# ldos.net
KiCad netlist of a schematic drawn in EasyEDA Pro
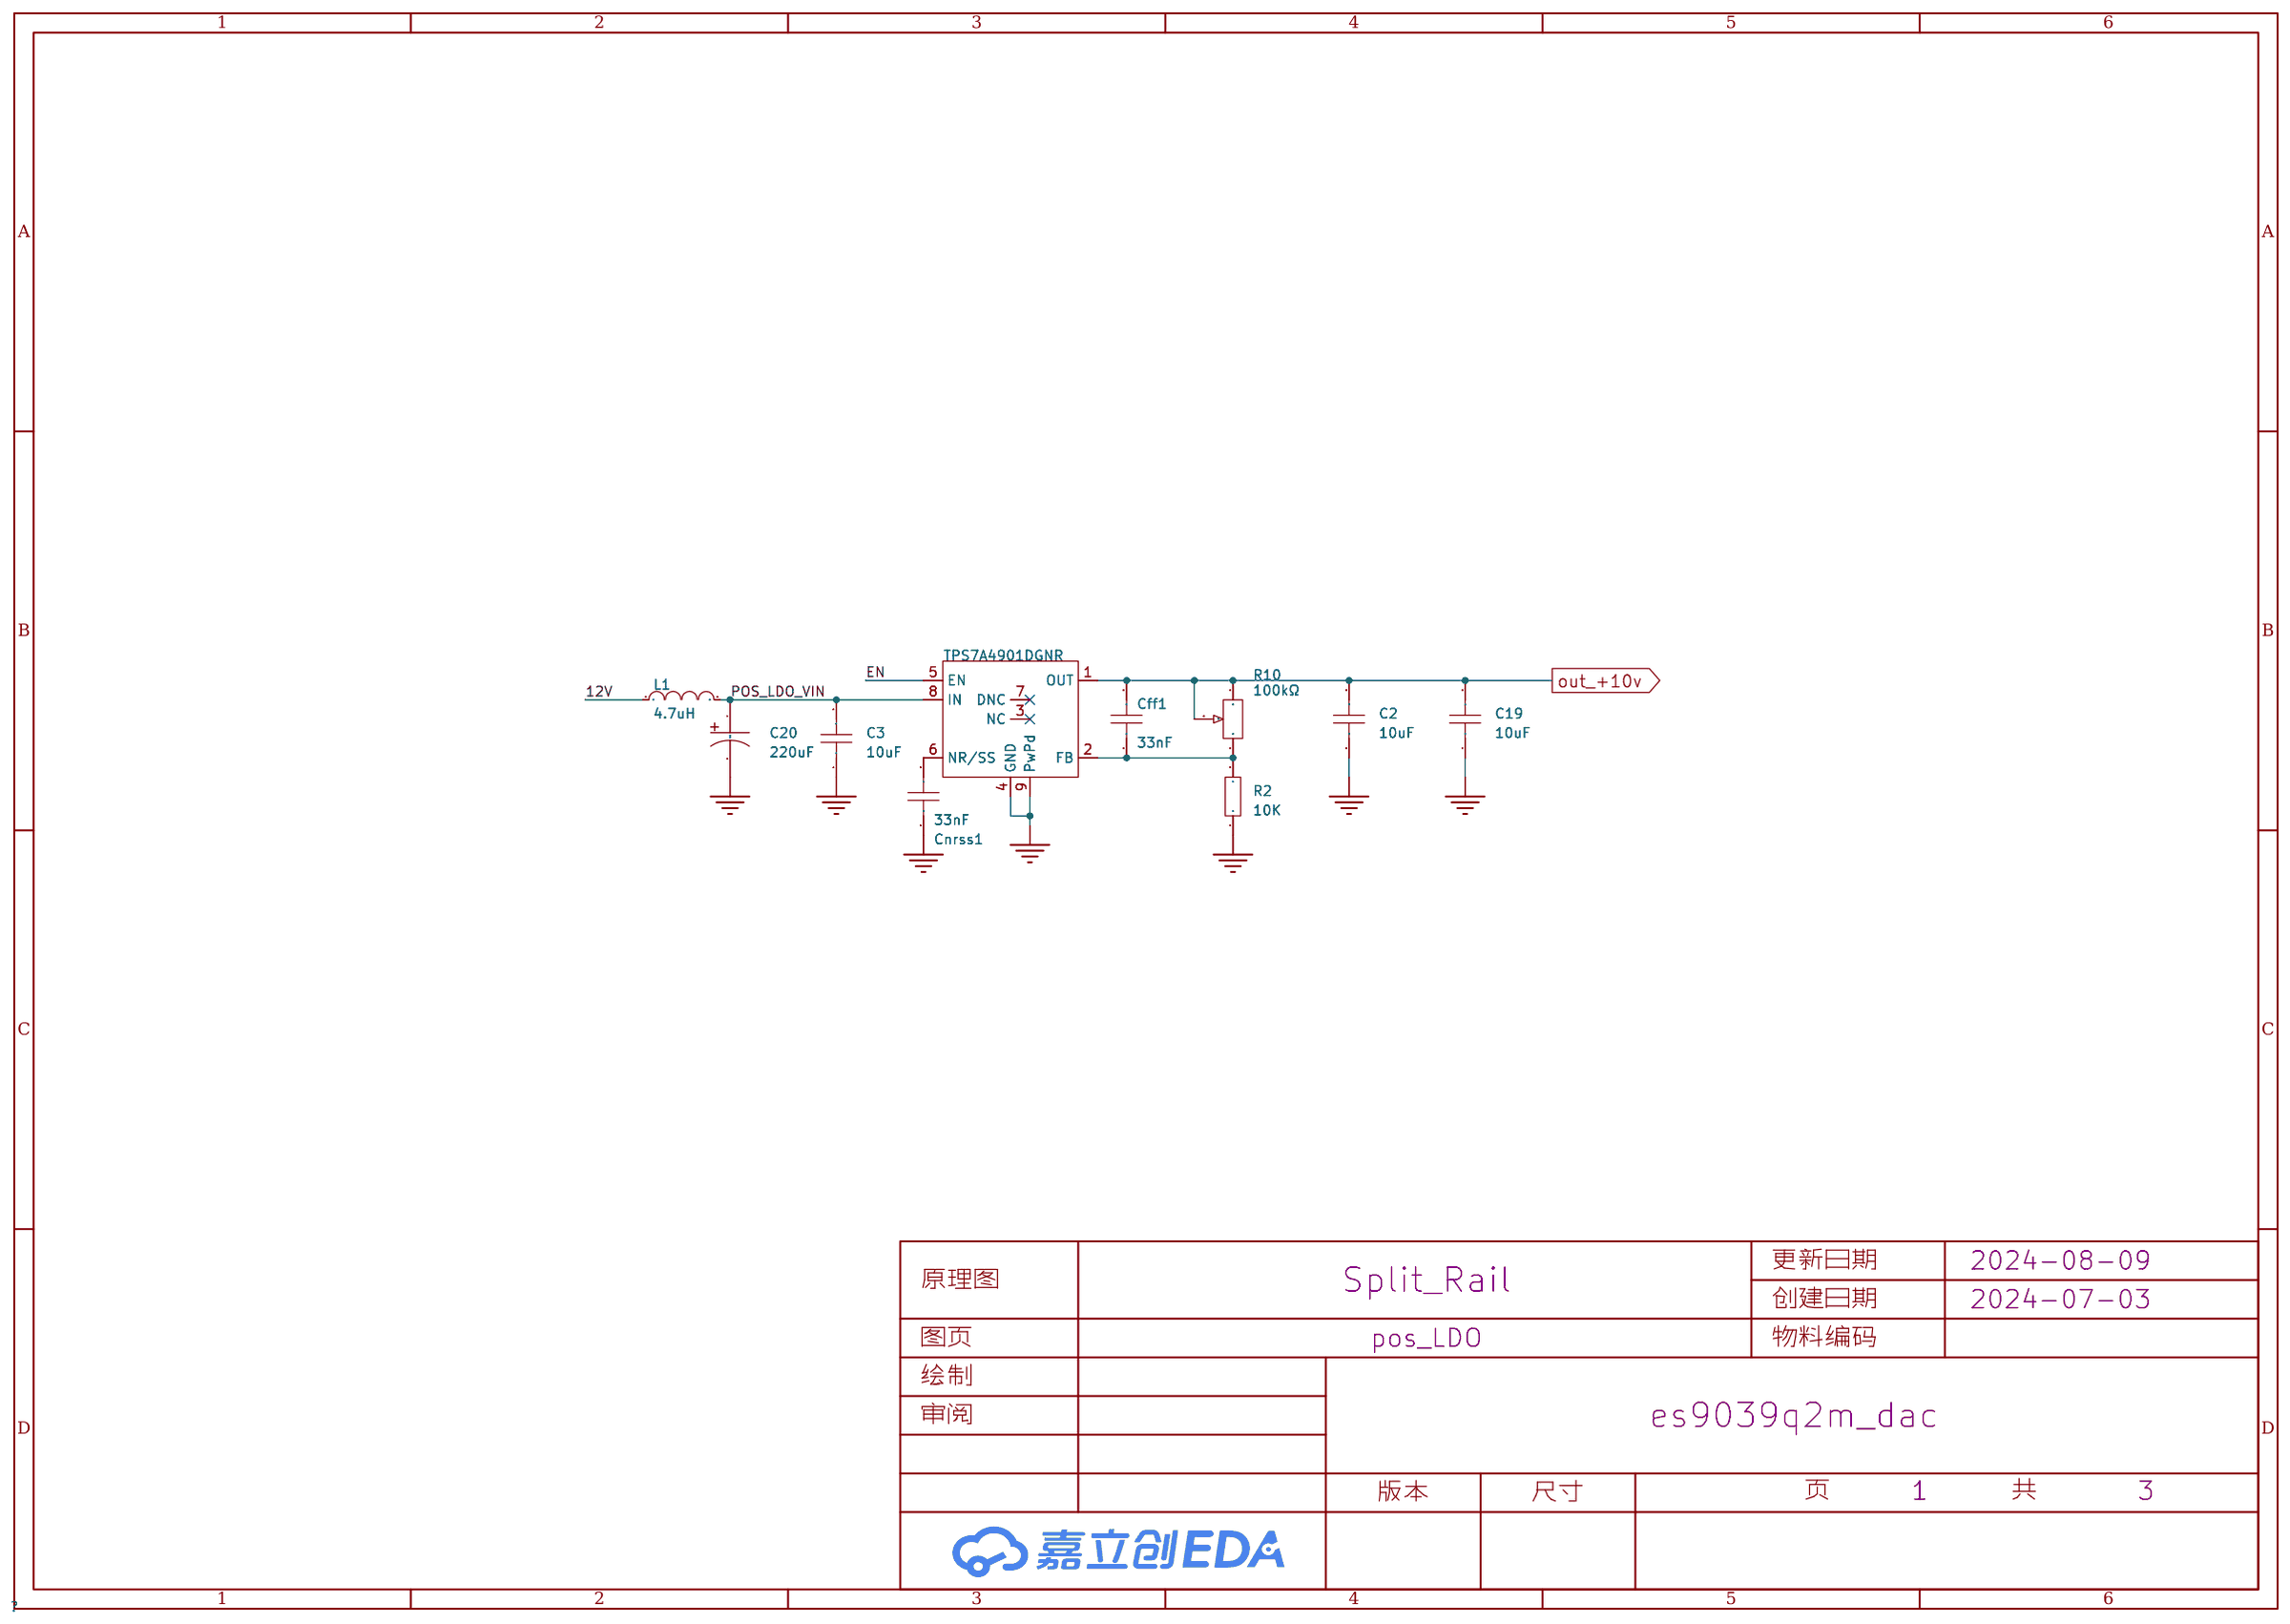
[diagram p0: pos_LDO]
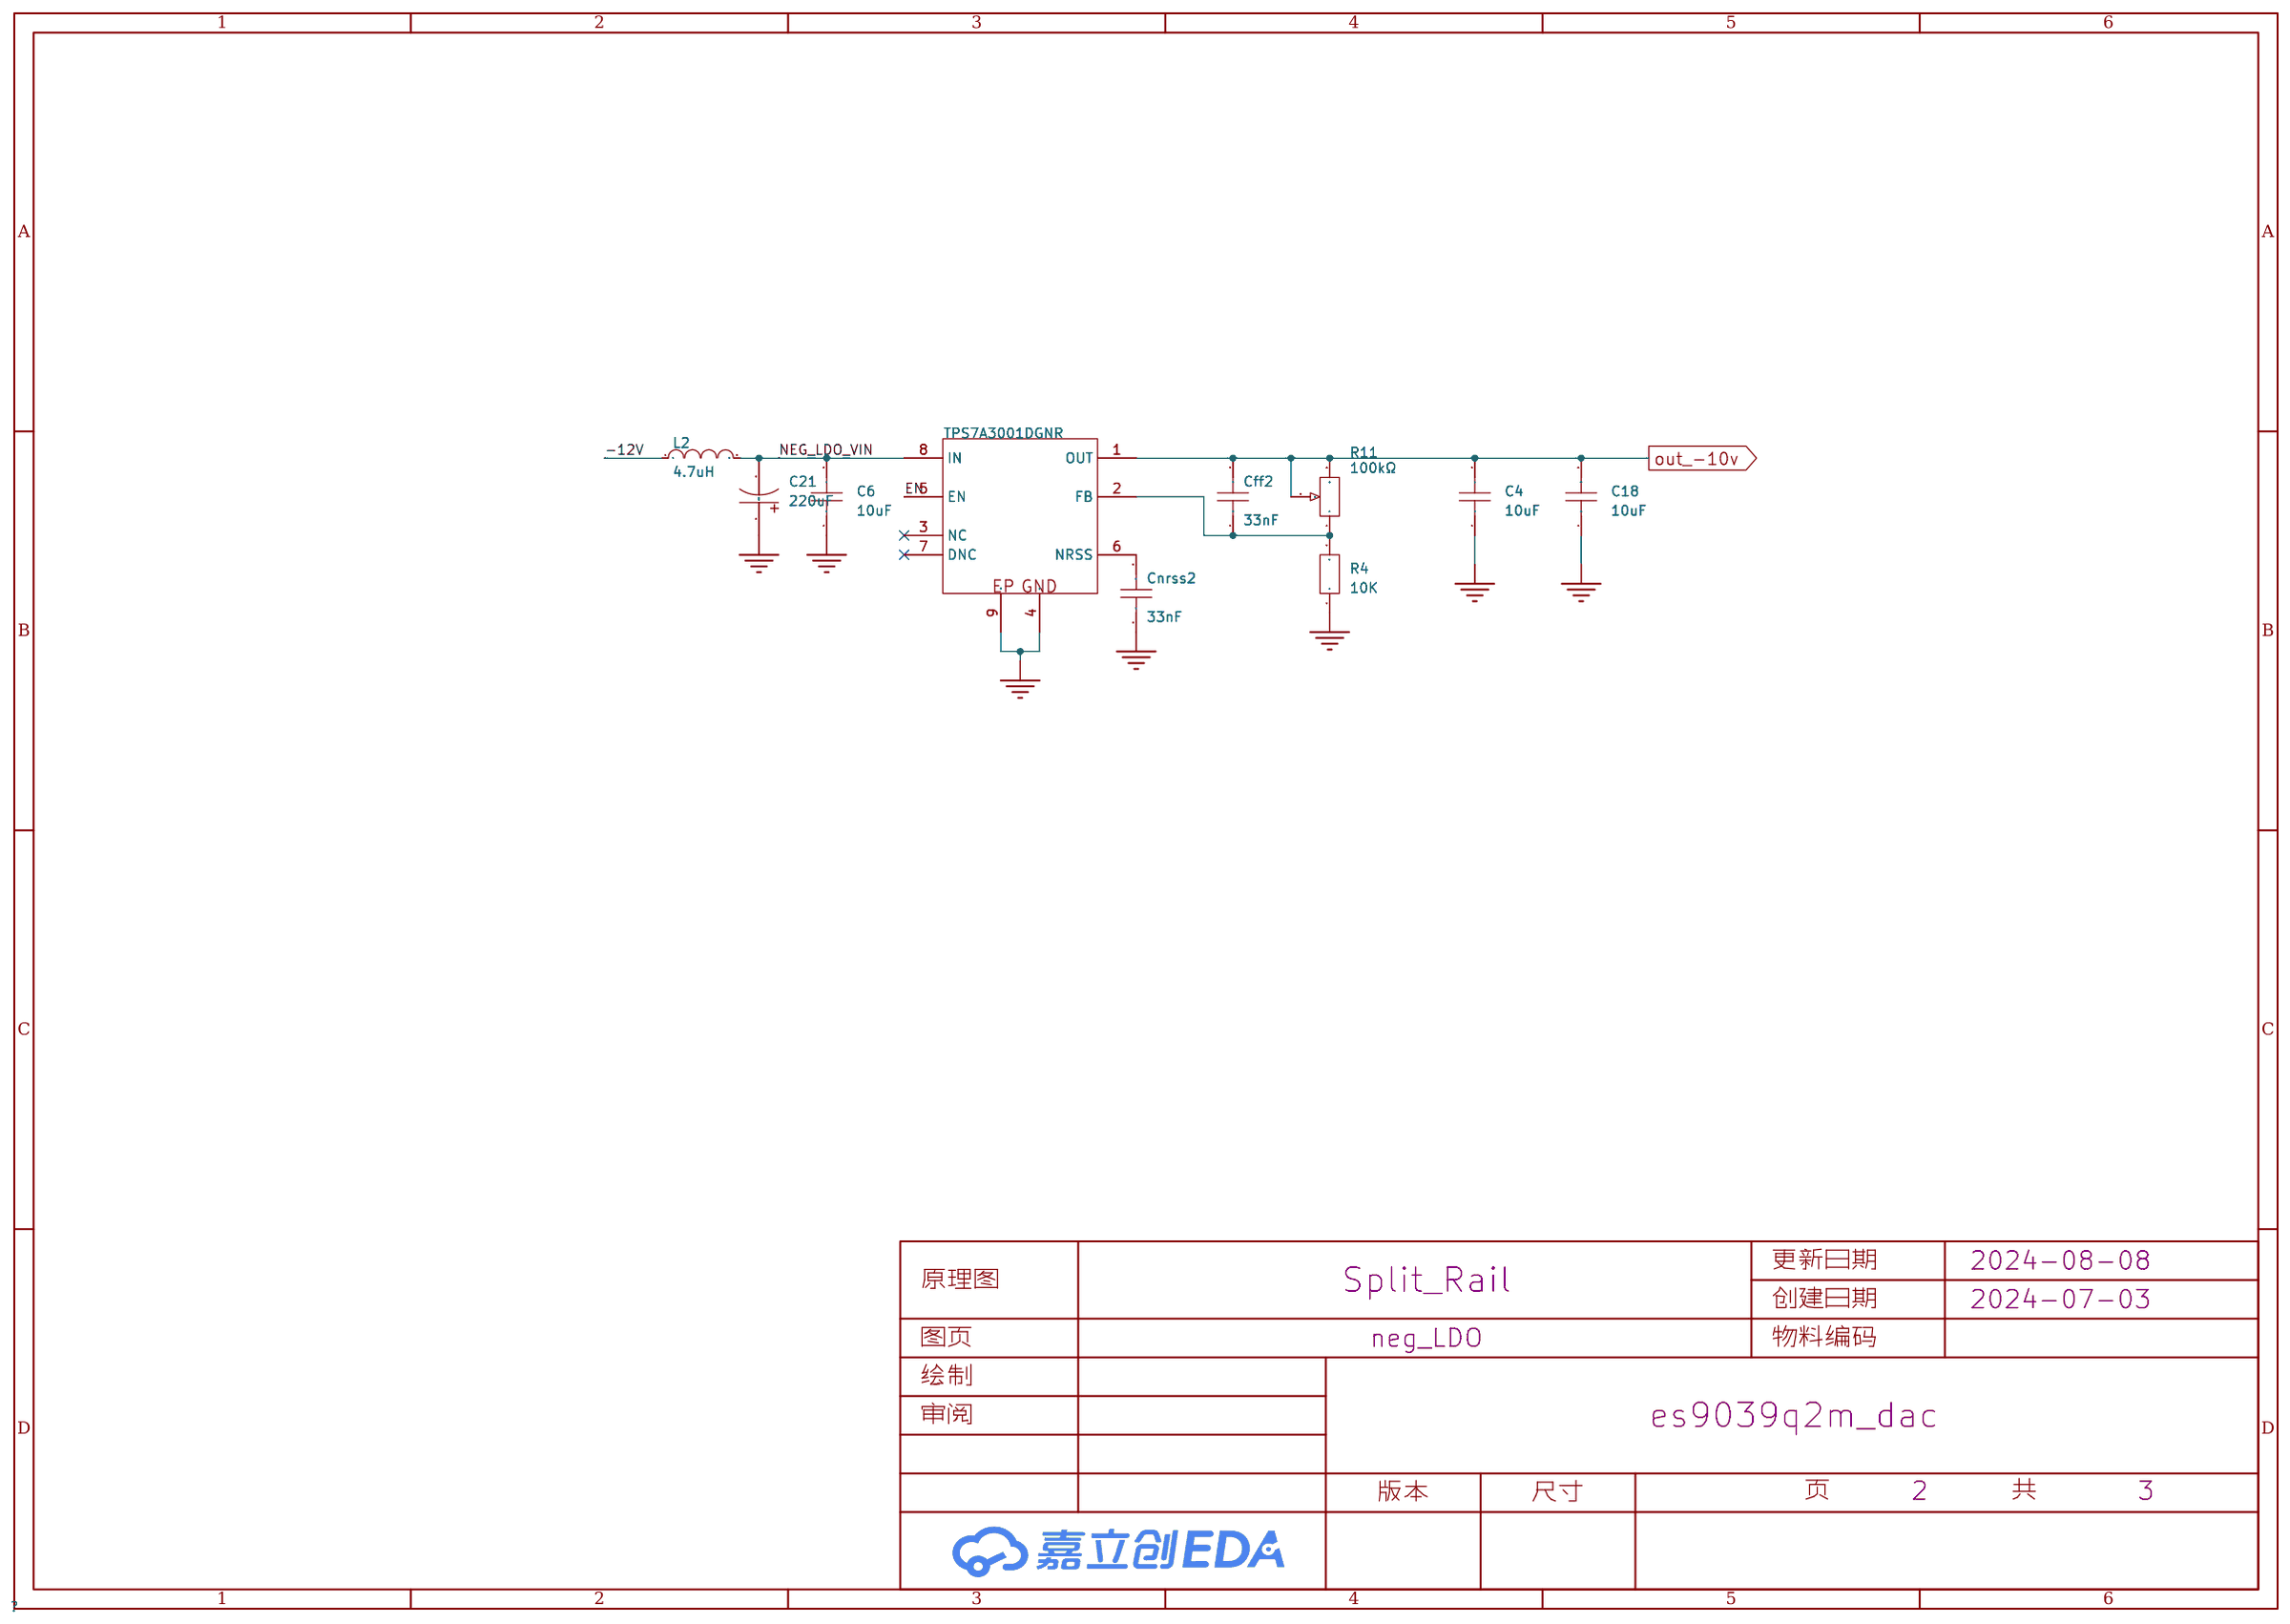
[diagram p1: neg_LDO]

(export (version "E")
  (design (tool "Eeschema 10.0.6"))
  (components
    (comp (ref "C2")
      (value "10uF")
      (footprint "easyedapro:C0805")
      (description "容值:10uF;精度:±10%;额定电压:16V;材质(温度系数):X7R;")
      (fields (field (name "Manufacturer Part") "0805B106K160NT") (field (name "Manufacturer") "FH(风华)"))
      (libsource (lib "easyedapro") (part "0805B106K160NT"))
    )
    (comp (ref "C3")
      (value "10uF")
      (footprint "easyedapro:C0805")
      (description "容值:10uF;精度:±10%;额定电压:16V;材质(温度系数):X7R;")
      (fields (field (name "Manufacturer Part") "0805B106K160NT") (field (name "Manufacturer") "FH(风华)"))
      (libsource (lib "easyedapro") (part "0805B106K160NT"))
    )
    (comp (ref "C19")
      (value "10uF")
      (footprint "easyedapro:C0805")
      (description "容值:10uF;精度:±10%;额定电压:16V;材质(温度系数):X7R;")
      (fields (field (name "Manufacturer Part") "0805B106K160NT") (field (name "Manufacturer") "FH(风华)"))
      (libsource (lib "easyedapro") (part "0805B106K160NT"))
    )
    (comp (ref "C20")
      (value "220uF")
      (footprint "easyedapro:CAP-TH_BD6.3-P2.50-D1.0-FD")
      (description "容值:220uF;精度:±20%;额定电压:16V;纹波电流:220mA@120Hz;等效串联电阻:-;")
      (fields
        (field (name "Manufacturer Part") "16PX220MEFC6.3*11")
        (field (name "Manufacturer") "rubycon(红宝石)")
      )
      (libsource (lib "easyedapro") (part "16PX220MEFC6.3*11"))
    )
    (comp (ref "Cff1")
      (value "33nF")
      (footprint "easyedapro:C1206")
      (description "容值:33nF;精度:±10%;额定电压:250V;材质(温度系数):X7R;")
      (fields
        (field (name "Manufacturer Part") "HHV1206R7333K251NSLJ")
        (field (name "Manufacturer") "Chinocera(华瓷)")
      )
      (libsource (lib "easyedapro") (part "HHV1206R7333K251NSLJ"))
    )
    (comp (ref "Cnrss1")
      (value "33nF")
      (footprint "easyedapro:C1206")
      (description "容值:33nF;精度:±10%;额定电压:250V;材质(温度系数):X7R;")
      (fields
        (field (name "Manufacturer Part") "HHV1206R7333K251NSLJ")
        (field (name "Manufacturer") "Chinocera(华瓷)")
      )
      (libsource (lib "easyedapro") (part "HHV1206R7333K251NSLJ"))
    )
    (comp (ref "L1")
      (value "4.7uH")
      (footprint "easyedapro:L1206")
      (description "电感值:4.7uH;精度:±10%;额定电流:25mA;饱和电流(Isat):-;直流电阻(DCR):650mΩ;")
      (fields (field (name "Manufacturer Part") "CMI321609U4R7KT") (field (name "Manufacturer") "FH(风华)"))
      (libsource (lib "easyedapro") (part "CMI321609U4R7KT"))
    )
    (comp (ref "R2") (value "10K") (footprint "easyedapro:R0603") (libsource (lib "easyedapro") (part "电阻")))
    (comp (ref "R10")
      (value "100kΩ")
      (footprint "easyedapro:RES-ADJ-TH_3P-L9.5-W4.9-P2.50-L_3296W")
      (description "阻值:100kΩ;精度:±10%;")
      (fields (field (name "Manufacturer Part") "3296W-1-104") (field (name "Manufacturer") "BOCHEN(博晨)"))
      (libsource (lib "easyedapro") (part "3296W-1-104"))
    )
    (comp (ref "U1")
      (value "TPS7A4901DGNR")
      (footprint "easyedapro:MSOP-8_L3.0-W3.0-P0.65-LS5.0-BL-EP")
      (description "输出类型:可调;最大输入电压:35V;输出电压:1.194V~33V;最大输出电流:150mA;电源纹波抑制比(PSRR):78dB@(1kHz);输出极性:正极;")
      (fields (field (name "Manufacturer") "TI(德州仪器)"))
      (libsource (lib "easyedapro") (part "TPS7A4901DGNR"))
    )
    (comp (ref "C4")
      (value "10uF")
      (footprint "easyedapro:C0805")
      (description "容值:10uF;精度:±10%;额定电压:16V;材质(温度系数):X7R;")
      (fields (field (name "Manufacturer Part") "0805B106K160NT") (field (name "Manufacturer") "FH(风华)"))
      (libsource (lib "easyedapro") (part "0805B106K160NT"))
    )
    (comp (ref "C6")
      (value "10uF")
      (footprint "easyedapro:C0805")
      (description "容值:10uF;精度:±10%;额定电压:16V;材质(温度系数):X7R;")
      (fields (field (name "Manufacturer Part") "0805B106K160NT") (field (name "Manufacturer") "FH(风华)"))
      (libsource (lib "easyedapro") (part "0805B106K160NT"))
    )
    (comp (ref "C18")
      (value "10uF")
      (footprint "easyedapro:C0805")
      (description "容值:10uF;精度:±10%;额定电压:16V;材质(温度系数):X7R;")
      (fields (field (name "Manufacturer Part") "0805B106K160NT") (field (name "Manufacturer") "FH(风华)"))
      (libsource (lib "easyedapro") (part "0805B106K160NT"))
    )
    (comp (ref "C21")
      (value "220uF")
      (footprint "easyedapro:CAP-TH_BD6.3-P2.50-D1.0-FD")
      (description "容值:220uF;精度:±20%;额定电压:16V;纹波电流:220mA@120Hz;等效串联电阻:-;")
      (fields
        (field (name "Manufacturer Part") "16PX220MEFC6.3*11")
        (field (name "Manufacturer") "rubycon(红宝石)")
      )
      (libsource (lib "easyedapro") (part "16PX220MEFC6.3*11"))
    )
    (comp (ref "Cff2")
      (value "33nF")
      (footprint "easyedapro:C1206")
      (description "容值:33nF;精度:±10%;额定电压:250V;材质(温度系数):X7R;")
      (fields
        (field (name "Manufacturer Part") "HHV1206R7333K251NSLJ")
        (field (name "Manufacturer") "Chinocera(华瓷)")
      )
      (libsource (lib "easyedapro") (part "HHV1206R7333K251NSLJ"))
    )
    (comp (ref "Cnrss2")
      (value "33nF")
      (footprint "easyedapro:C1206")
      (description "容值:33nF;精度:±10%;额定电压:250V;材质(温度系数):X7R;")
      (fields
        (field (name "Manufacturer Part") "HHV1206R7333K251NSLJ")
        (field (name "Manufacturer") "Chinocera(华瓷)")
      )
      (libsource (lib "easyedapro") (part "HHV1206R7333K251NSLJ"))
    )
    (comp (ref "L2")
      (value "4.7uH")
      (footprint "easyedapro:L1206")
      (description "电感值:4.7uH;精度:±10%;额定电流:25mA;饱和电流(Isat):-;直流电阻(DCR):650mΩ;")
      (fields (field (name "Manufacturer Part") "CMI321609U4R7KT") (field (name "Manufacturer") "FH(风华)"))
      (libsource (lib "easyedapro") (part "CMI321609U4R7KT"))
    )
    (comp (ref "R4") (value "10K") (libsource (lib "easyedapro") (part "RT0603BRD074K7L")))
    (comp (ref "R11")
      (value "100kΩ")
      (footprint "easyedapro:RES-ADJ-TH_3P-L9.5-W4.9-P2.50-L_3296W")
      (description "阻值:100kΩ;精度:±10%;")
      (fields (field (name "Manufacturer Part") "3296W-1-104") (field (name "Manufacturer") "BOCHEN(博晨)"))
      (libsource (lib "easyedapro") (part "3296W-1-104"))
    )
    (comp (ref "U2")
      (value "TPS7A3001DGNR")
      (footprint "easyedapro:MSOP-8_L3.0-W3.0-P0.65-LS5.0-BL-EP")
      (description "输出类型:可调;最大输入电压:35V;输出电压:1.18V~33V;最大输出电流:200mA;电源纹波抑制比(PSRR):72dB@(120Hz);输出极性:负极;")
      (fields (field (name "Manufacturer") "TI(德州仪器)"))
      (libsource (lib "easyedapro") (part "TPS7A3001DGNR"))
    )
  )
  (nets
    (net (code "1") (name "-12V") (class "Default")
      (node (ref "L2") (pin "1") (pinfunction "1_1") (pintype "unspecified"))
    )
    (net (code "2") (name "12V") (class "Default")
      (node (ref "L1") (pin "1") (pinfunction "1_1") (pintype "unspecified"))
    )
    (net (code "3") (name "EN") (class "Default")
      (node (ref "U1") (pin "5") (pinfunction "EN_5") (pintype "input"))
      (node (ref "U2") (pin "5") (pinfunction "EN_5") (pintype "input"))
    )
    (net (code "4") (name "GND") (class "Default")
      (node (ref "C18") (pin "1") (pinfunction "1_1") (pintype "unspecified"))
      (node (ref "C19") (pin "1") (pinfunction "1_1") (pintype "unspecified"))
      (node (ref "C2") (pin "1") (pinfunction "1_1") (pintype "unspecified"))
      (node (ref "C20") (pin "2") (pinfunction "2_2") (pintype "unspecified"))
      (node (ref "C21") (pin "1") (pinfunction "1_1") (pintype "unspecified"))
      (node (ref "C3") (pin "1") (pinfunction "1_1") (pintype "unspecified"))
      (node (ref "C4") (pin "1") (pinfunction "1_1") (pintype "unspecified"))
      (node (ref "C6") (pin "1") (pinfunction "1_1") (pintype "unspecified"))
      (node (ref "Cnrss1") (pin "1") (pinfunction "1_1") (pintype "unspecified"))
      (node (ref "Cnrss2") (pin "1") (pinfunction "1_1") (pintype "unspecified"))
      (node (ref "R2") (pin "1") (pinfunction "1_1") (pintype "input"))
      (node (ref "R4") (pin "1") (pinfunction "1_1") (pintype "unspecified"))
      (node (ref "U1") (pin "4") (pinfunction "GND_4") (pintype "input"))
      (node (ref "U1") (pin "9") (pinfunction "PwPd_9") (pintype "input"))
      (node (ref "U2") (pin "4") (pinfunction "GND_4") (pintype "input"))
      (node (ref "U2") (pin "9") (pinfunction "EP_9") (pintype "input"))
    )
    (net (code "5") (name "NEG_LDO_VIN") (class "Default")
      (node (ref "C21") (pin "2") (pinfunction "2_2") (pintype "unspecified"))
      (node (ref "C6") (pin "2") (pinfunction "2_2") (pintype "unspecified"))
      (node (ref "L2") (pin "2") (pinfunction "2_2") (pintype "unspecified"))
      (node (ref "U2") (pin "8") (pinfunction "IN_8") (pintype "input"))
    )
    (net (code "6") (name "Net-(U1-FB)") (class "Default")
      (node (ref "Cff1") (pin "1") (pinfunction "1_1") (pintype "unspecified"))
      (node (ref "R10") (pin "1") (pinfunction "1_1") (pintype "input"))
      (node (ref "R2") (pin "2") (pinfunction "2_2") (pintype "input"))
      (node (ref "U1") (pin "2") (pinfunction "FB_2") (pintype "input"))
    )
    (net (code "7") (name "Net-(U1-NR{slash}SS)") (class "Default")
      (node (ref "Cnrss1") (pin "2") (pinfunction "2_2") (pintype "unspecified"))
      (node (ref "U1") (pin "6") (pinfunction "NR/SS_6") (pintype "input"))
    )
    (net (code "8") (name "Net-(U2-FB)") (class "Default")
      (node (ref "Cff2") (pin "1") (pinfunction "1_1") (pintype "unspecified"))
      (node (ref "R11") (pin "1") (pinfunction "1_1") (pintype "input"))
      (node (ref "R4") (pin "2") (pinfunction "2_2") (pintype "unspecified"))
      (node (ref "U2") (pin "2") (pinfunction "FB_2") (pintype "input"))
    )
    (net (code "9") (name "Net-(U2-NRSS)") (class "Default")
      (node (ref "Cnrss2") (pin "2") (pinfunction "2_2") (pintype "unspecified"))
      (node (ref "U2") (pin "6") (pinfunction "NRSS_6") (pintype "input"))
    )
    (net (code "10") (name "POS_LDO_VIN") (class "Default")
      (node (ref "C20") (pin "1") (pinfunction "1_1") (pintype "unspecified"))
      (node (ref "C3") (pin "2") (pinfunction "2_2") (pintype "unspecified"))
      (node (ref "L1") (pin "2") (pinfunction "2_2") (pintype "unspecified"))
      (node (ref "U1") (pin "8") (pinfunction "IN_8") (pintype "input"))
    )
    (net (code "11") (name "out_+10v") (class "Default")
      (node (ref "C19") (pin "2") (pinfunction "2_2") (pintype "unspecified"))
      (node (ref "C2") (pin "2") (pinfunction "2_2") (pintype "unspecified"))
      (node (ref "Cff1") (pin "2") (pinfunction "2_2") (pintype "unspecified"))
      (node (ref "R10") (pin "2") (pinfunction "2_2") (pintype "input"))
      (node (ref "R10") (pin "3") (pinfunction "3_3") (pintype "input"))
      (node (ref "U1") (pin "1") (pinfunction "OUT_1") (pintype "input"))
    )
    (net (code "12") (name "out_-10v") (class "Default")
      (node (ref "C18") (pin "2") (pinfunction "2_2") (pintype "unspecified"))
      (node (ref "C4") (pin "2") (pinfunction "2_2") (pintype "unspecified"))
      (node (ref "Cff2") (pin "2") (pinfunction "2_2") (pintype "unspecified"))
      (node (ref "R11") (pin "2") (pinfunction "2_2") (pintype "input"))
      (node (ref "R11") (pin "3") (pinfunction "3_3") (pintype "input"))
      (node (ref "U2") (pin "1") (pinfunction "OUT_1") (pintype "input"))
    )
    (net (code "13") (name "unconnected-(U1-DNC-Pad7)") (class "Default")
      (node (ref "U1") (pin "7") (pinfunction "DNC_7") (pintype "input+no_connect"))
    )
    (net (code "14") (name "unconnected-(U1-NC-Pad3)") (class "Default")
      (node (ref "U1") (pin "3") (pinfunction "NC_3") (pintype "input+no_connect"))
    )
    (net (code "15") (name "unconnected-(U2-DNC-Pad7)") (class "Default")
      (node (ref "U2") (pin "7") (pinfunction "DNC_7") (pintype "input+no_connect"))
    )
    (net (code "16") (name "unconnected-(U2-NC-Pad3)") (class "Default")
      (node (ref "U2") (pin "3") (pinfunction "NC_3") (pintype "input+no_connect"))
    )
  )
)
